# CompressorWithDualLED.net
KiCad netlist of a schematic drawn in Altium Designer
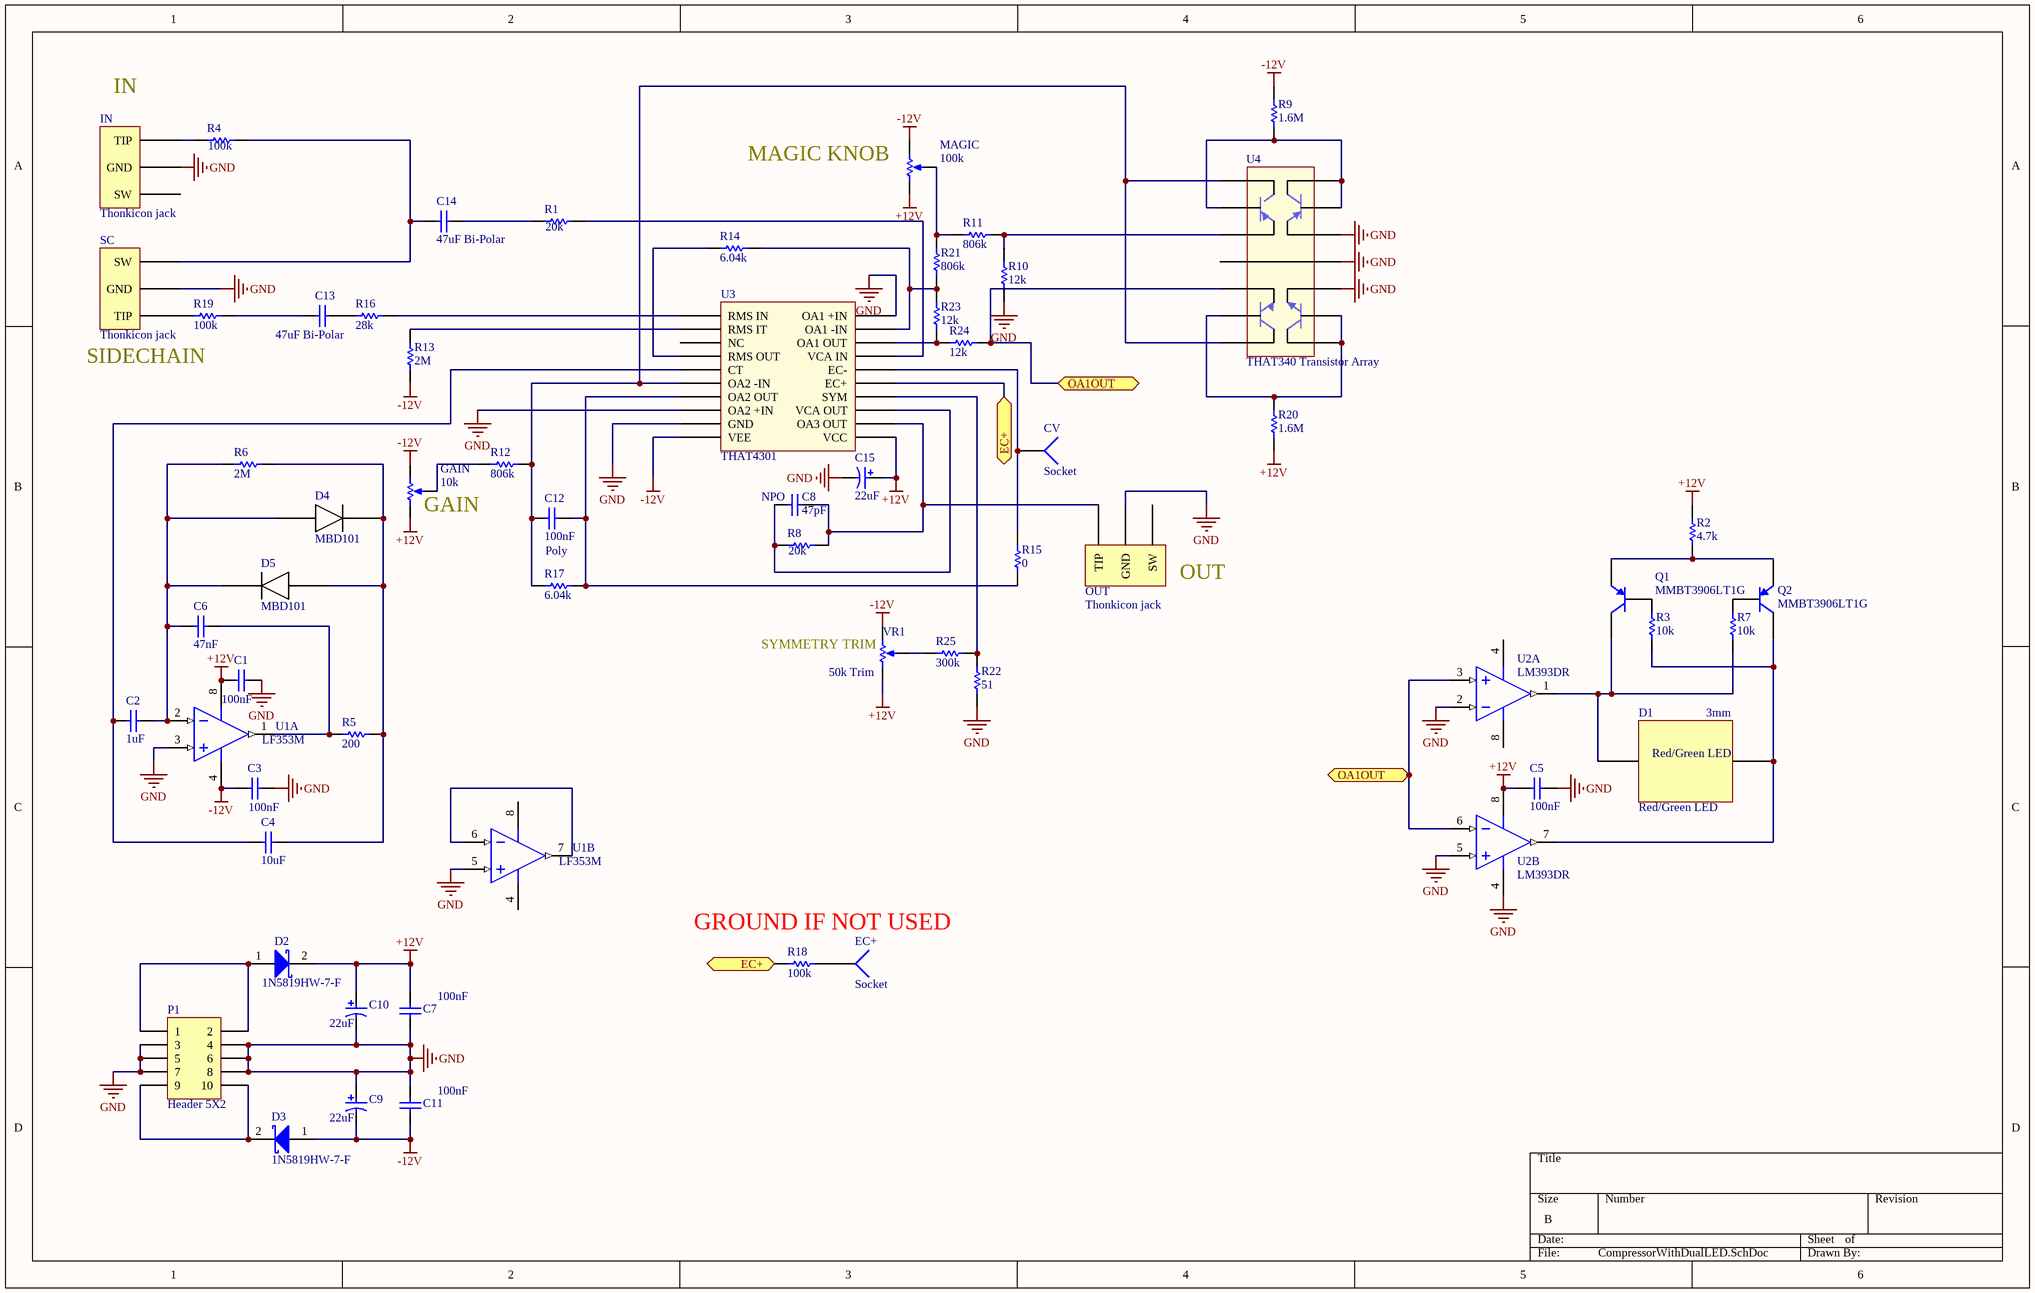
[diagram p0: CompressorWithDualLED.SchDoc]

(export (version "E")
  (design (tool "Eeschema 10.0.6"))
  (components
    (comp (ref "C1")
      (value "100nF")
      (footprint "CAPC0603(1608)100_M")
      (description "CAP")
      (fields (field (name "MFR") "AVX"))
      (libsource (lib "Altium Content Vault") (part "CMP-1035-00002-1"))
    )
    (comp (ref "C2")
      (value "1uF")
      (footprint "CAPC0805(2012)155_L")
      (description "CAP 4.7uF 10V ±10% 0805 (2012 Metric) Thickness 1.55mm SMD")
      (fields (field (name "TOLERANCE") "Â±10%") (field (name "MFR") "Murata"))
      (libsource (lib "Altium Content Vault") (part "CMP-1036-04882-1"))
    )
    (comp (ref "C3")
      (value "100nF")
      (footprint "CAPC0603(1608)100_M")
      (description "CAP")
      (fields (field (name "MFR") "AVX"))
      (libsource (lib "Altium Content Vault") (part "CMP-1035-00002-1"))
    )
    (comp (ref "C4")
      (value "10uF")
      (footprint "CAPC0805(2012)155_L")
      (description "CAP 4.7uF 10V ±10% 0805 (2012 Metric) Thickness 1.55mm SMD")
      (fields (field (name "TOLERANCE") "Â±10%") (field (name "MFR") "Murata"))
      (libsource (lib "Altium Content Vault") (part "CMP-1036-04882-1"))
    )
    (comp (ref "C5")
      (value "100nF")
      (footprint "CAPC0603(1608)100_M")
      (description "CAP")
      (fields (field (name "MFR") "AVX"))
      (libsource (lib "Altium Content Vault") (part "CMP-1035-00002-1"))
    )
    (comp (ref "C6")
      (value "47nF")
      (footprint "1608[0603]")
      (description "CAP 47uF 10V ±20% 1206 (3216 Metric) Thickness 1.9mm SMD")
      (fields (field (name "TOLERANCE") "Â±20%") (field (name "MFR") "Murata"))
      (libsource (lib "altium-import") (part "root_2_CMP-1037-05002-1_"))
    )
    (comp (ref "C7")
      (value "100nF")
      (footprint "CAPC0603(1608)100_M")
      (description "CAP")
      (fields (field (name "MFR") "AVX"))
      (libsource (lib "Altium Content Vault") (part "CMP-1035-00002-1"))
    )
    (comp (ref "C8")
      (value "47pF")
      (footprint "CAPC0603(1608)100_M")
      (description "CAP 5.1pF 25V ±0.5pF 0603 (1608 Metric) Thickness 1mm SMD")
      (fields (field (name "TOLERANCE") "Â±0.5pF") (field (name "TYPE") "NPO") (field (name "MFR") "Yageo"))
      (libsource (lib "Altium Content Vault") (part "CMP-1035-00351-1"))
    )
    (comp (ref "C9")
      (value "22uF")
      (footprint "NIC-CAPA2-4X5.8_V")
      (fields (field (name "MFR") "Kemet"))
      (libsource (lib "Altium Content Vault") (part "CMP-0687-00016-1"))
    )
    (comp (ref "C10")
      (value "22uF")
      (footprint "NIC-CAPA2-4X5.8_V")
      (fields (field (name "MFR") "Kemet"))
      (libsource (lib "Altium Content Vault") (part "CMP-0687-00016-1"))
    )
    (comp (ref "C11")
      (value "100nF")
      (footprint "CAPC0603(1608)100_M")
      (description "CAP")
      (fields (field (name "MFR") "AVX"))
      (libsource (lib "Altium Content Vault") (part "CMP-1035-00002-1"))
    )
    (comp (ref "C12")
      (value "100nF")
      (footprint "WIMA Poly Cap")
      (description "CAP 47uF 10V ±20% 1206 (3216 Metric) Thickness 1.9mm SMD")
      (fields (field (name "TOLERANCE") "Â±20%") (field (name "TYPE") "Poly") (field (name "MFR") "WIMA"))
      (libsource (lib "altium-import") (part "root_2_CAP_"))
    )
    (comp (ref "C13")
      (value "47uF Bi-Polar")
      (footprint "Nichicon Bi-Polar 6.3mm")
      (description "CAP 47uF 10V ±20% 1206 (3216 Metric) Thickness 1.9mm SMD")
      (fields (field (name "TOLERANCE") "Â±20%") (field (name "MFR") "Nichicon"))
      (libsource (lib "altium-import") (part "root_2_CAP_"))
    )
    (comp (ref "C14")
      (value "47uF Bi-Polar")
      (footprint "Nichicon Bi-Polar 6.3mm")
      (description "CAP 47uF 10V ±20% 1206 (3216 Metric) Thickness 1.9mm SMD")
      (fields (field (name "TOLERANCE") "Â±20%") (field (name "MFR") "Nichicon"))
      (libsource (lib "altium-import") (part "root_2_CAP_"))
    )
    (comp (ref "C15")
      (value "22uF")
      (footprint "NIC-CAPA2-4X5.8_V")
      (fields (field (name "MFR") "Kemet"))
      (libsource (lib "Altium Content Vault") (part "CMP-0687-00016-1"))
    )
    (comp (ref "CV")
      (value "Socket")
      (footprint "PIN1")
      (fields (field (name "PUBLISHER") "Altium Limited"))
      (libsource (lib "Miscellaneous Connectors") (part "Socket"))
    )
    (comp (ref "D1")
      (value "Red/Green LED")
      (footprint "Red/Green LED")
      (fields (field (name "MFR") "Lumex") (field (name "SIZE") "3mm"))
      (libsource (lib "EurrackParts") (part "Red/Green LED"))
    )
    (comp (ref "D2")
      (value "1N5819HW-7-F")
      (footprint "DIOD-SOD-123-2_V")
      (fields (field (name "MFR") "Diodes Inc."))
      (libsource (lib "Altium Content Vault") (part "CMP-0303-00003-1"))
    )
    (comp (ref "D3")
      (value "1N5819HW-7-F")
      (footprint "DIOD-SOD-123-2_V")
      (fields (field (name "MFR") "Diodes Inc."))
      (libsource (lib "Altium Content Vault") (part "CMP-0303-00003-1"))
    )
    (comp (ref "D4") (value "MBD101") (footprint "SOT23_L") (libsource (lib "EurrackParts") (part "MBD101")))
    (comp (ref "D5") (value "MBD101") (footprint "SOT23_L") (libsource (lib "EurrackParts") (part "MBD101")))
    (comp (ref "EC+")
      (value "Socket")
      (footprint "PIN1")
      (fields (field (name "PUBLISHER") "Altium Limited"))
      (libsource (lib "Miscellaneous Connectors") (part "Socket"))
    )
    (comp (ref "GAIN")
      (value "10k")
      (footprint "SonGueiPot")
      (fields (field (name "MANUFACTURER") "Bourns") (field (name "PARTNUMBER") "3006P-7-502ZLF"))
      (libsource (lib "altium-import") (part "root_3_BOUR-3006P-3_"))
    )
    (comp (ref "IN")
      (value "Thonkicon jack")
      (footprint "Thonkiconn Pot PJ301M")
      (libsource (lib "EurrackParts") (part "Thonkicon jack"))
    )
    (comp (ref "MAGIC")
      (value "100k")
      (footprint "SonGueiPot")
      (fields (field (name "MANUFACTURER") "Bourns") (field (name "PARTNUMBER") "3006P-7-502ZLF"))
      (libsource (lib "altium-import") (part "root_3_BOUR-3006P-3_"))
    )
    (comp (ref "OUT")
      (value "Thonkicon jack")
      (footprint "Thonkiconn Pot PJ301M")
      (libsource (lib "") (part "Thonkicon jack_1"))
    )
    (comp (ref "P1")
      (value "Header 5X2")
      (footprint "HDR2X5")
      (description "Header, 5-Pin, Dual row")
      (fields (field (name "PUBLISHER") "Altium Limited"))
      (libsource (lib "Miscellaneous Connectors") (part "Header 5X2"))
    )
    (comp (ref "Q1")
      (value "MMBT3906LT1G")
      (footprint "SOT23_M")
      (description "PNP General Purpose Amplifier")
      (fields (field (name "MFR") "On Semi") (field (name "PUBLISHER") "Altium Limited"))
      (libsource (lib "Miscellaneous Devices") (part "2N3906"))
    )
    (comp (ref "Q2")
      (value "MMBT3906LT1G")
      (footprint "SOT23_M")
      (description "PNP General Purpose Amplifier")
      (fields (field (name "MFR") "On Semi") (field (name "PUBLISHER") "Altium Limited"))
      (libsource (lib "Miscellaneous Devices") (part "2N3906"))
    )
    (comp (ref "R1")
      (value "20k")
      (footprint "RESC0603(1608)_M")
      (description "Res")
      (fields (field (name "TOLERANCE") "1%") (field (name "MFR") "Yageo"))
      (libsource (lib "Altium Content Vault") (part "CMP-1012-00002-1"))
    )
    (comp (ref "R2")
      (value "4.7k")
      (footprint "RESC0603(1608)_M")
      (description "Res")
      (fields (field (name "TOLERANCE") "5 %") (field (name "MFR") "Susumu"))
      (libsource (lib "Altium Content Vault") (part "CMP-1012-00002-1"))
    )
    (comp (ref "R3")
      (value "10k")
      (footprint "RESC0603(1608)_M")
      (description "Res")
      (fields (field (name "TOLERANCE") "5 %") (field (name "MFR") "Yageo"))
      (libsource (lib "Altium Content Vault") (part "CMP-1012-00002-1"))
    )
    (comp (ref "R4")
      (value "100k")
      (footprint "RESC0603(1608)_M")
      (description "Thin Film Resistor")
      (fields (field (name "TOLERANCE") "1 %") (field (name "MFR") "Yageo"))
      (libsource (lib "Altium Content Vault") (part "CMP-1012-00002-1"))
    )
    (comp (ref "R5")
      (value "200")
      (footprint "RESC0603(1608)_M")
      (description "Res")
      (fields (field (name "TOLERANCE") "5 %") (field (name "MFR") "Yageo"))
      (libsource (lib "Altium Content Vault") (part "CMP-1012-00002-1"))
    )
    (comp (ref "R6")
      (value "2M")
      (footprint "RESC0603(1608)_M")
      (description "Res")
      (fields (field (name "TOLERANCE") "5 %") (field (name "MFR") "Yageo"))
      (libsource (lib "Altium Content Vault") (part "CMP-1012-00002-1"))
    )
    (comp (ref "R7")
      (value "10k")
      (footprint "RESC0603(1608)_M")
      (description "Res")
      (fields (field (name "TOLERANCE") "5 %") (field (name "MFR") "Yageo"))
      (libsource (lib "Altium Content Vault") (part "CMP-1012-00002-1"))
    )
    (comp (ref "R8")
      (value "20k")
      (footprint "RESC0603(1608)_M")
      (description "Res")
      (fields (field (name "TOLERANCE") "1%") (field (name "MFR") "Yageo"))
      (libsource (lib "Altium Content Vault") (part "CMP-1012-00002-1"))
    )
    (comp (ref "R9")
      (value "1.6M")
      (footprint "RESC0603(1608)_M")
      (description "Res")
      (fields (field (name "TOLERANCE") "5 %") (field (name "MFR") "Yageo"))
      (libsource (lib "Altium Content Vault") (part "CMP-1012-00002-1"))
    )
    (comp (ref "R10")
      (value "12k")
      (footprint "RESC0603(1608)_M")
      (description "Res")
      (fields (field (name "TOLERANCE") "5 %") (field (name "MFR") "Yageo"))
      (libsource (lib "Altium Content Vault") (part "CMP-1012-00002-1"))
    )
    (comp (ref "R11")
      (value "806k")
      (footprint "6-0805_L")
      (description "Res")
      (fields (field (name "TOLERANCE") "5 %") (field (name "MFR") "Yageo"))
      (libsource (lib "altium-import") (part "root_0_CMP-1012-00002-1_"))
    )
    (comp (ref "R12")
      (value "806k")
      (footprint "6-0805_L")
      (description "Res")
      (fields (field (name "TOLERANCE") "5 %") (field (name "MFR") "Yageo"))
      (libsource (lib "altium-import") (part "root_0_CMP-1012-00002-1_"))
    )
    (comp (ref "R13")
      (value "2M")
      (footprint "RESC0603(1608)_M")
      (description "Res")
      (fields (field (name "TOLERANCE") "5 %") (field (name "MFR") "Yageo"))
      (libsource (lib "Altium Content Vault") (part "CMP-1012-00002-1"))
    )
    (comp (ref "R14")
      (value "6.04k")
      (footprint "6-0805_L")
      (description "Res")
      (fields (field (name "TOLERANCE") "5 %") (field (name "MFR") "TE Connectivity"))
      (libsource (lib "altium-import") (part "root_2_CMP-1012-00002-1_"))
    )
    (comp (ref "R15")
      (value "0")
      (footprint "RESC0603(1608)_M")
      (description "Res")
      (fields (field (name "TOLERANCE") "5 %") (field (name "MFR") "Vishay"))
      (libsource (lib "Altium Content Vault") (part "CMP-1012-00002-1"))
    )
    (comp (ref "R16")
      (value "28k")
      (footprint "RESC0603(1608)_M")
      (description "Res")
      (fields (field (name "TOLERANCE") ".1%") (field (name "MFR") "Yageo"))
      (libsource (lib "Altium Content Vault") (part "CMP-1012-00002-1"))
    )
    (comp (ref "R17")
      (value "6.04k")
      (footprint "6-0805_L")
      (description "Res")
      (fields (field (name "TOLERANCE") "5 %") (field (name "MFR") "TE Connectivity"))
      (libsource (lib "altium-import") (part "root_2_CMP-1012-00002-1_"))
    )
    (comp (ref "R18")
      (value "100k")
      (footprint "RESC0603(1608)_M")
      (description "Thin Film Resistor")
      (fields (field (name "TOLERANCE") "1 %") (field (name "MFR") "Yageo"))
      (libsource (lib "Altium Content Vault") (part "CMP-1012-00002-1"))
    )
    (comp (ref "R19")
      (value "100k")
      (footprint "RESC0603(1608)_M")
      (description "Thin Film Resistor")
      (fields (field (name "TOLERANCE") "1 %") (field (name "MFR") "Yageo"))
      (libsource (lib "Altium Content Vault") (part "CMP-1012-00002-1"))
    )
    (comp (ref "R20")
      (value "1.6M")
      (footprint "RESC0603(1608)_M")
      (description "Res")
      (fields (field (name "TOLERANCE") "5 %") (field (name "MFR") "Yageo"))
      (libsource (lib "Altium Content Vault") (part "CMP-1012-00002-1"))
    )
    (comp (ref "R21")
      (value "806k")
      (footprint "6-0805_L")
      (description "Res")
      (fields (field (name "TOLERANCE") "5 %") (field (name "MFR") "Yageo"))
      (libsource (lib "altium-import") (part "root_1_CMP-1012-00002-1_"))
    )
    (comp (ref "R22")
      (value "51")
      (footprint "RESC0603(1608)_M")
      (description "Res")
      (fields (field (name "TOLERANCE") "5 %") (field (name "MFR") "Yageo"))
      (libsource (lib "Altium Content Vault") (part "CMP-1012-00002-1"))
    )
    (comp (ref "R23")
      (value "12k")
      (footprint "RESC0603(1608)_M")
      (description "Res")
      (fields (field (name "TOLERANCE") "5 %") (field (name "MFR") "Yageo"))
      (libsource (lib "Altium Content Vault") (part "CMP-1012-00002-1"))
    )
    (comp (ref "R24")
      (value "12k")
      (footprint "RESC0603(1608)_M")
      (description "Res")
      (fields (field (name "TOLERANCE") "5 %") (field (name "MFR") "Yageo"))
      (libsource (lib "Altium Content Vault") (part "CMP-1012-00002-1"))
    )
    (comp (ref "R25")
      (value "300k")
      (footprint "RESC0603(1608)_M")
      (description "Res")
      (fields (field (name "TOLERANCE") "5 %") (field (name "MFR") "Yageo"))
      (libsource (lib "Altium Content Vault") (part "CMP-1012-00002-1"))
    )
    (comp (ref "SC")
      (value "Thonkicon jack")
      (footprint "Thonkiconn Pot PJ301M")
      (libsource (lib "") (part "Thonkicon jack_1"))
    )
    (comp (ref "U1")
      (value "LF353M")
      (footprint "D0008A_M")
      (description "Wide Bandwidth Dual JFET Input Operational Amplifier, 8-pin Narrow SOIC")
      (fields (field (name "MANUFACTURER") "Texas Instruments"))
      (libsource (lib "Altium Content Vault") (part "CMP-0055-00855-3"))
    )
    (comp (ref "U2")
      (value "LM393DR")
      (footprint "D0008A_L")
      (description "Low Power Low Offset Voltage Dual Comparator, 8-pin Narrow SOIC")
      (fields (field (name "MANUFACTURER") "Texas Instruments"))
      (libsource (lib "altium-import") (part "root_2_mirrored_CMP-0055-00682-3_"))
    )
    (comp (ref "U3")
      (value "THAT4301")
      (footprint "SOIC20THAT")
      (fields (field (name "MFR") "THAT Corp"))
      (libsource (lib "EurrackParts") (part "THAT4301"))
    )
    (comp (ref "U4")
      (value "THAT340 Transistor Array")
      (footprint "SOIC14")
      (fields (field (name "MFR") "THAT Corp"))
      (libsource (lib "EurrackParts") (part "THAT340"))
    )
    (comp (ref "VR1")
      (value "50k Trim")
      (footprint "BOUR-3362P")
      (description "Square Trimpot(R) Trimming Potentiometer, 10 KOhm, 300 V, -55 to 125 degC, 3-Pin THD, RoHS, Tube")
      (fields (field (name "TOLERANCE") "1%") (field (name "MFR") "Bourns"))
      (libsource (lib "Altium Content Vault") (part "CMP-1747-00004-1"))
    )
  )
  (nets
    (net (code "1") (name "+12V") (class "Default")
      (node (ref "C1") (pin "1") (pinfunction "1_1") (pintype "passive"))
      (node (ref "C10") (pin "1") (pinfunction "1_1") (pintype "passive"))
      (node (ref "C15") (pin "1") (pinfunction "1_1") (pintype "passive"))
      (node (ref "C5") (pin "1") (pinfunction "1_1") (pintype "passive"))
      (node (ref "C7") (pin "1") (pinfunction "1_1") (pintype "passive"))
      (node (ref "D2") (pin "2") (pinfunction "K_2") (pintype "passive"))
      (node (ref "GAIN") (pin "3") (pinfunction "CW_3") (pintype "passive"))
      (node (ref "MAGIC") (pin "3") (pinfunction "CW_3") (pintype "passive"))
      (node (ref "R2") (pin "1") (pinfunction "1_1") (pintype "passive"))
      (node (ref "R20") (pin "2") (pinfunction "2_2") (pintype "passive"))
      (node (ref "U1") (pin "8") (pinfunction "V+_8") (pintype "power_in"))
      (node (ref "U2") (pin "8") (pinfunction "V+_8") (pintype "power_in"))
      (node (ref "U3") (pin "11") (pinfunction "VCC_11") (pintype "passive"))
      (node (ref "VR1") (pin "1") (pinfunction "CCW_1") (pintype "passive"))
    )
    (net (code "2") (name "-12V") (class "Default")
      (node (ref "C11") (pin "2") (pinfunction "2_2") (pintype "passive"))
      (node (ref "C3") (pin "1") (pinfunction "1_1") (pintype "passive"))
      (node (ref "C9") (pin "2") (pinfunction "2_2") (pintype "passive"))
      (node (ref "D3") (pin "1") (pinfunction "A_1") (pintype "passive"))
      (node (ref "GAIN") (pin "1") (pinfunction "CCW_1") (pintype "passive"))
      (node (ref "MAGIC") (pin "1") (pinfunction "CCW_1") (pintype "passive"))
      (node (ref "R13") (pin "1") (pinfunction "1_1") (pintype "passive"))
      (node (ref "R9") (pin "1") (pinfunction "1_1") (pintype "passive"))
      (node (ref "U1") (pin "4") (pinfunction "V-_4") (pintype "power_in"))
      (node (ref "U3") (pin "10") (pinfunction "VEE_10") (pintype "passive"))
      (node (ref "VR1") (pin "3") (pinfunction "CW_3") (pintype "passive"))
    )
    (net (code "3") (name "/EC+") (class "Default")
      (node (ref "R18") (pin "2") (pinfunction "2_2") (pintype "passive"))
      (node (ref "U3") (pin "15") (pinfunction "EC+_15") (pintype "passive"))
    )
    (net (code "4") (name "/OA1OUT") (class "Default")
      (node (ref "R24") (pin "1") (pinfunction "1_1") (pintype "passive"))
      (node (ref "U2") (pin "3") (pinfunction "INA+_3") (pintype "input"))
      (node (ref "U2") (pin "6") (pinfunction "INB-_6") (pintype "input"))
      (node (ref "U4") (pin "12") (pinfunction "C_12") (pintype "passive"))
    )
    (net (code "5") (name "GND") (class "Default")
      (node (ref "C1") (pin "2") (pinfunction "2_2") (pintype "passive"))
      (node (ref "C10") (pin "2") (pinfunction "2_2") (pintype "passive"))
      (node (ref "C11") (pin "1") (pinfunction "1_1") (pintype "passive"))
      (node (ref "C15") (pin "2") (pinfunction "2_2") (pintype "passive"))
      (node (ref "C3") (pin "2") (pinfunction "2_2") (pintype "passive"))
      (node (ref "C5") (pin "2") (pinfunction "2_2") (pintype "passive"))
      (node (ref "C7") (pin "2") (pinfunction "2_2") (pintype "passive"))
      (node (ref "C9") (pin "1") (pinfunction "1_1") (pintype "passive"))
      (node (ref "IN") (pin "1") (pinfunction "GND_1") (pintype "passive"))
      (node (ref "OUT") (pin "1") (pinfunction "GND_1") (pintype "passive"))
      (node (ref "P1") (pin "3") (pinfunction "3_3") (pintype "passive"))
      (node (ref "P1") (pin "4") (pinfunction "4_4") (pintype "passive"))
      (node (ref "P1") (pin "5") (pinfunction "5_5") (pintype "passive"))
      (node (ref "P1") (pin "6") (pinfunction "6_6") (pintype "passive"))
      (node (ref "P1") (pin "7") (pinfunction "7_7") (pintype "passive"))
      (node (ref "P1") (pin "8") (pinfunction "8_8") (pintype "passive"))
      (node (ref "R10") (pin "1") (pinfunction "1_1") (pintype "passive"))
      (node (ref "R22") (pin "2") (pinfunction "2_2") (pintype "passive"))
      (node (ref "SC") (pin "1") (pinfunction "GND_1") (pintype "passive"))
      (node (ref "U1") (pin "3") (pinfunction "INA+_3") (pintype "input"))
      (node (ref "U1") (pin "5") (pinfunction "INB+_5") (pintype "input"))
      (node (ref "U2") (pin "2") (pinfunction "INA-_2") (pintype "input"))
      (node (ref "U2") (pin "4") (pinfunction "GND_4") (pintype "power_in"))
      (node (ref "U2") (pin "5") (pinfunction "INB+_5") (pintype "input"))
      (node (ref "U3") (pin "20") (pinfunction "OA1_+IN_20") (pintype "passive"))
      (node (ref "U3") (pin "8") (pinfunction "OA2_+IN_8") (pintype "passive"))
      (node (ref "U3") (pin "9") (pinfunction "GND_9") (pintype "passive"))
      (node (ref "U4") (pin "3") (pinfunction "E_3") (pintype "passive"))
      (node (ref "U4") (pin "4") (pinfunction "E_4") (pintype "passive"))
      (node (ref "U4") (pin "5") (pinfunction "E_5") (pintype "passive"))
    )
    (net (code "6") (name "Net-(C4-Pad2)") (class "Default")
      (node (ref "C4") (pin "2") (pinfunction "2_2") (pintype "passive"))
      (node (ref "D4") (pin "1") (pinfunction "1_1") (pintype "passive"))
      (node (ref "D5") (pin "3") (pinfunction "3_3") (pintype "passive"))
      (node (ref "R5") (pin "1") (pinfunction "1_1") (pintype "passive"))
      (node (ref "R6") (pin "1") (pinfunction "1_1") (pintype "passive"))
    )
    (net (code "7") (name "Net-(C13-Pad1)") (class "Default")
      (node (ref "C13") (pin "1") (pinfunction "1_1") (pintype "passive"))
      (node (ref "R16") (pin "1") (pinfunction "1_1") (pintype "passive"))
    )
    (net (code "8") (name "Net-(C13-Pad2)") (class "Default")
      (node (ref "C13") (pin "2") (pinfunction "2_2") (pintype "passive"))
      (node (ref "R19") (pin "1") (pinfunction "1_1") (pintype "passive"))
    )
    (net (code "9") (name "Net-(C14-Pad1)") (class "Default")
      (node (ref "C14") (pin "1") (pinfunction "1_1") (pintype "passive"))
      (node (ref "R1") (pin "2") (pinfunction "2_2") (pintype "passive"))
    )
    (net (code "10") (name "Net-(D2-A)") (class "Default")
      (node (ref "D2") (pin "1") (pinfunction "A_1") (pintype "passive"))
      (node (ref "P1") (pin "1") (pinfunction "1_1") (pintype "passive"))
      (node (ref "P1") (pin "2") (pinfunction "2_2") (pintype "passive"))
    )
    (net (code "11") (name "Net-(D3-K)") (class "Default")
      (node (ref "D3") (pin "2") (pinfunction "K_2") (pintype "passive"))
      (node (ref "P1") (pin "10") (pinfunction "10_10") (pintype "passive"))
      (node (ref "P1") (pin "9") (pinfunction "9_9") (pintype "passive"))
    )
    (net (code "12") (name "Net-(EC+-Pad1)") (class "Default")
      (node (ref "EC+") (pin "1") (pinfunction "1_1") (pintype "passive"))
      (node (ref "R18") (pin "1") (pinfunction "1_1") (pintype "passive"))
    )
    (net (code "13") (name "Net-(GAIN-WIPER)") (class "Default")
      (node (ref "GAIN") (pin "2") (pinfunction "WIPER_2") (pintype "passive"))
      (node (ref "R12") (pin "1") (pinfunction "1_1") (pintype "passive"))
    )
    (net (code "14") (name "Net-(IN-TIP)") (class "Default")
      (node (ref "IN") (pin "3") (pinfunction "TIP_3") (pintype "passive"))
      (node (ref "R4") (pin "2") (pinfunction "2_2") (pintype "passive"))
    )
    (net (code "15") (name "Net-(MAGIC-WIPER)") (class "Default")
      (node (ref "MAGIC") (pin "2") (pinfunction "WIPER_2") (pintype "passive"))
      (node (ref "R11") (pin "1") (pinfunction "1_1") (pintype "passive"))
      (node (ref "R21") (pin "2") (pinfunction "2_2") (pintype "passive"))
    )
    (net (code "16") (name "Net-(OUT-TIP)") (class "Default")
      (node (ref "C8") (pin "2") (pinfunction "2_2") (pintype "passive"))
      (node (ref "OUT") (pin "3") (pinfunction "TIP_3") (pintype "passive"))
      (node (ref "R8") (pin "1") (pinfunction "1_1") (pintype "passive"))
      (node (ref "U3") (pin "12") (pinfunction "OA3_OUT_12") (pintype "passive"))
    )
    (net (code "17") (name "Net-(Q1-B)") (class "Default")
      (node (ref "Q1") (pin "2") (pinfunction "B_2") (pintype "passive"))
      (node (ref "R3") (pin "1") (pinfunction "1_1") (pintype "passive"))
    )
    (net (code "18") (name "Net-(Q1-C)") (class "Default")
      (node (ref "D1") (pin "1") (pinfunction "1_1") (pintype "passive"))
      (node (ref "Q1") (pin "3") (pinfunction "C_3") (pintype "passive"))
      (node (ref "R7") (pin "2") (pinfunction "2_2") (pintype "passive"))
      (node (ref "U2") (pin "1") (pinfunction "OUTA_1") (pintype "output"))
    )
    (net (code "19") (name "Net-(Q1-E)") (class "Default")
      (node (ref "Q1") (pin "1") (pinfunction "E_1") (pintype "passive"))
      (node (ref "Q2") (pin "1") (pinfunction "E_1") (pintype "passive"))
      (node (ref "R2") (pin "2") (pinfunction "2_2") (pintype "passive"))
    )
    (net (code "20") (name "Net-(Q2-B)") (class "Default")
      (node (ref "Q2") (pin "2") (pinfunction "B_2") (pintype "passive"))
      (node (ref "R7") (pin "1") (pinfunction "1_1") (pintype "passive"))
    )
    (net (code "21") (name "Net-(Q2-C)") (class "Default")
      (node (ref "D1") (pin "2") (pinfunction "2_2") (pintype "passive"))
      (node (ref "Q2") (pin "3") (pinfunction "C_3") (pintype "passive"))
      (node (ref "R3") (pin "2") (pinfunction "2_2") (pintype "passive"))
      (node (ref "U2") (pin "7") (pinfunction "OUTB_7") (pintype "output"))
    )
    (net (code "22") (name "Net-(R9-Pad2)") (class "Default")
      (node (ref "R9") (pin "2") (pinfunction "2_2") (pintype "passive"))
      (node (ref "U4") (pin "6") (pinfunction "B_6") (pintype "passive"))
      (node (ref "U4") (pin "7") (pinfunction "C_7") (pintype "passive"))
      (node (ref "U4") (pin "9") (pinfunction "B_9") (pintype "passive"))
    )
    (net (code "23") (name "Net-(R10-Pad2)") (class "Default")
      (node (ref "R10") (pin "2") (pinfunction "2_2") (pintype "passive"))
      (node (ref "R11") (pin "2") (pinfunction "2_2") (pintype "passive"))
      (node (ref "U4") (pin "10") (pinfunction "C_10") (pintype "passive"))
    )
    (net (code "24") (name "Net-(R20-Pad1)") (class "Default")
      (node (ref "R20") (pin "1") (pinfunction "1_1") (pintype "passive"))
      (node (ref "U4") (pin "1") (pinfunction "C_1") (pintype "passive"))
      (node (ref "U4") (pin "13") (pinfunction "B_13") (pintype "passive"))
      (node (ref "U4") (pin "2") (pinfunction "B_2") (pintype "passive"))
    )
    (net (code "25") (name "Net-(SC-SW)") (class "Default")
      (node (ref "C14") (pin "2") (pinfunction "2_2") (pintype "passive"))
      (node (ref "R4") (pin "1") (pinfunction "1_1") (pintype "passive"))
      (node (ref "SC") (pin "2") (pinfunction "SW_2") (pintype "passive"))
    )
    (net (code "26") (name "Net-(SC-TIP)") (class "Default")
      (node (ref "R19") (pin "2") (pinfunction "2_2") (pintype "passive"))
      (node (ref "SC") (pin "3") (pinfunction "TIP_3") (pintype "passive"))
    )
    (net (code "27") (name "Net-(U1A-INA-)") (class "Default")
      (node (ref "C2") (pin "2") (pinfunction "2_2") (pintype "passive"))
      (node (ref "C6") (pin "2") (pinfunction "2_2") (pintype "passive"))
      (node (ref "D4") (pin "3") (pinfunction "3_3") (pintype "passive"))
      (node (ref "D5") (pin "1") (pinfunction "1_1") (pintype "passive"))
      (node (ref "R6") (pin "2") (pinfunction "2_2") (pintype "passive"))
      (node (ref "U1") (pin "2") (pinfunction "INA-_2") (pintype "input"))
    )
    (net (code "28") (name "Net-(U1A-OUTA)") (class "Default")
      (node (ref "C6") (pin "1") (pinfunction "1_1") (pintype "passive"))
      (node (ref "R5") (pin "2") (pinfunction "2_2") (pintype "passive"))
      (node (ref "U1") (pin "1") (pinfunction "OUTA_1") (pintype "output"))
    )
    (net (code "29") (name "Net-(U1B-INB-)") (class "Default")
      (node (ref "U1") (pin "6") (pinfunction "INB-_6") (pintype "input"))
      (node (ref "U1") (pin "7") (pinfunction "OUTB_7") (pintype "output"))
    )
    (net (code "30") (name "Net-(U3-CT)") (class "Default")
      (node (ref "C2") (pin "1") (pinfunction "1_1") (pintype "passive"))
      (node (ref "C4") (pin "1") (pinfunction "1_1") (pintype "passive"))
      (node (ref "U3") (pin "5") (pinfunction "CT_5") (pintype "passive"))
    )
    (net (code "31") (name "Net-(U3-EC-)") (class "Default")
      (node (ref "CV") (pin "1") (pinfunction "1_1") (pintype "passive"))
      (node (ref "R15") (pin "1") (pinfunction "1_1") (pintype "passive"))
      (node (ref "U3") (pin "16") (pinfunction "EC-_16") (pintype "passive"))
    )
    (net (code "32") (name "Net-(U3-OA1_-IN)") (class "Default")
      (node (ref "R14") (pin "1") (pinfunction "1_1") (pintype "passive"))
      (node (ref "R21") (pin "1") (pinfunction "1_1") (pintype "passive"))
      (node (ref "R23") (pin "2") (pinfunction "2_2") (pintype "passive"))
      (node (ref "U3") (pin "19") (pinfunction "OA1_-IN_19") (pintype "passive"))
    )
    (net (code "33") (name "Net-(U3-OA1_OUT)") (class "Default")
      (node (ref "R23") (pin "1") (pinfunction "1_1") (pintype "passive"))
      (node (ref "R24") (pin "2") (pinfunction "2_2") (pintype "passive"))
      (node (ref "U3") (pin "18") (pinfunction "OA1_OUT_18") (pintype "passive"))
    )
    (net (code "34") (name "Net-(U3-OA2_-IN)") (class "Default")
      (node (ref "C12") (pin "2") (pinfunction "2_2") (pintype "passive"))
      (node (ref "R12") (pin "2") (pinfunction "2_2") (pintype "passive"))
      (node (ref "R17") (pin "2") (pinfunction "2_2") (pintype "passive"))
      (node (ref "U3") (pin "6") (pinfunction "OA2_-IN_6") (pintype "passive"))
      (node (ref "U4") (pin "14") (pinfunction "E_14") (pintype "passive"))
      (node (ref "U4") (pin "8") (pinfunction "E_8") (pintype "passive"))
    )
    (net (code "35") (name "Net-(U3-OA2_OUT)") (class "Default")
      (node (ref "C12") (pin "1") (pinfunction "1_1") (pintype "passive"))
      (node (ref "R15") (pin "2") (pinfunction "2_2") (pintype "passive"))
      (node (ref "R17") (pin "1") (pinfunction "1_1") (pintype "passive"))
      (node (ref "U3") (pin "7") (pinfunction "OA2_OUT_7") (pintype "passive"))
    )
    (net (code "36") (name "Net-(U3-RMS_IN)") (class "Default")
      (node (ref "R16") (pin "2") (pinfunction "2_2") (pintype "passive"))
      (node (ref "U3") (pin "1") (pinfunction "RMS_IN_1") (pintype "passive"))
    )
    (net (code "37") (name "Net-(U3-RMS_IT)") (class "Default")
      (node (ref "R13") (pin "2") (pinfunction "2_2") (pintype "passive"))
      (node (ref "U3") (pin "2") (pinfunction "RMS_IT_2") (pintype "passive"))
    )
    (net (code "38") (name "Net-(U3-RMS_OUT)") (class "Default")
      (node (ref "R14") (pin "2") (pinfunction "2_2") (pintype "passive"))
      (node (ref "U3") (pin "4") (pinfunction "RMS_OUT_4") (pintype "passive"))
    )
    (net (code "39") (name "Net-(U3-SYM)") (class "Default")
      (node (ref "R22") (pin "1") (pinfunction "1_1") (pintype "passive"))
      (node (ref "R25") (pin "1") (pinfunction "1_1") (pintype "passive"))
      (node (ref "U3") (pin "14") (pinfunction "SYM_14") (pintype "passive"))
    )
    (net (code "40") (name "Net-(U3-VCA_IN)") (class "Default")
      (node (ref "R1") (pin "1") (pinfunction "1_1") (pintype "passive"))
      (node (ref "U3") (pin "17") (pinfunction "VCA_IN_17") (pintype "passive"))
    )
    (net (code "41") (name "Net-(U3-VCA_OUT)") (class "Default")
      (node (ref "C8") (pin "1") (pinfunction "1_1") (pintype "passive"))
      (node (ref "R8") (pin "2") (pinfunction "2_2") (pintype "passive"))
      (node (ref "U3") (pin "13") (pinfunction "VCA_OUT_13") (pintype "passive"))
    )
    (net (code "42") (name "Net-(VR1-S)") (class "Default")
      (node (ref "R25") (pin "2") (pinfunction "2_2") (pintype "passive"))
      (node (ref "VR1") (pin "2") (pinfunction "S_2") (pintype "passive"))
    )
    (net (code "43") (name "unconnected-(IN-SW-Pad2)") (class "Default")
      (node (ref "IN") (pin "2") (pinfunction "SW_2") (pintype "passive"))
    )
    (net (code "44") (name "unconnected-(OUT-SW-Pad2)") (class "Default")
      (node (ref "OUT") (pin "2") (pinfunction "SW_2") (pintype "passive"))
    )
    (net (code "45") (name "unconnected-(U1B-V+-Pad8)") (class "Default")
      (node (ref "U1") (pin "8") (pinfunction "V+_8") (pintype "power_in"))
    )
    (net (code "46") (name "unconnected-(U1B-V--Pad4)") (class "Default")
      (node (ref "U1") (pin "4") (pinfunction "V-_4") (pintype "power_in"))
    )
    (net (code "47") (name "unconnected-(U2A-GND-Pad4)") (class "Default")
      (node (ref "U2") (pin "4") (pinfunction "GND_4") (pintype "power_in"))
    )
    (net (code "48") (name "unconnected-(U2A-V+-Pad8)") (class "Default")
      (node (ref "U2") (pin "8") (pinfunction "V+_8") (pintype "power_in"))
    )
    (net (code "49") (name "unconnected-(U3-NC-Pad3)") (class "Default")
      (node (ref "U3") (pin "3") (pinfunction "NC_3") (pintype "passive"))
    )
    (net (code "50") (name "unconnected-(U4-E-Pad11)") (class "Default")
      (node (ref "U4") (pin "11") (pinfunction "E_11") (pintype "passive"))
    )
  )
)
